# OfflineSWD.net
KiCad netlist of a schematic drawn in Altium Designer
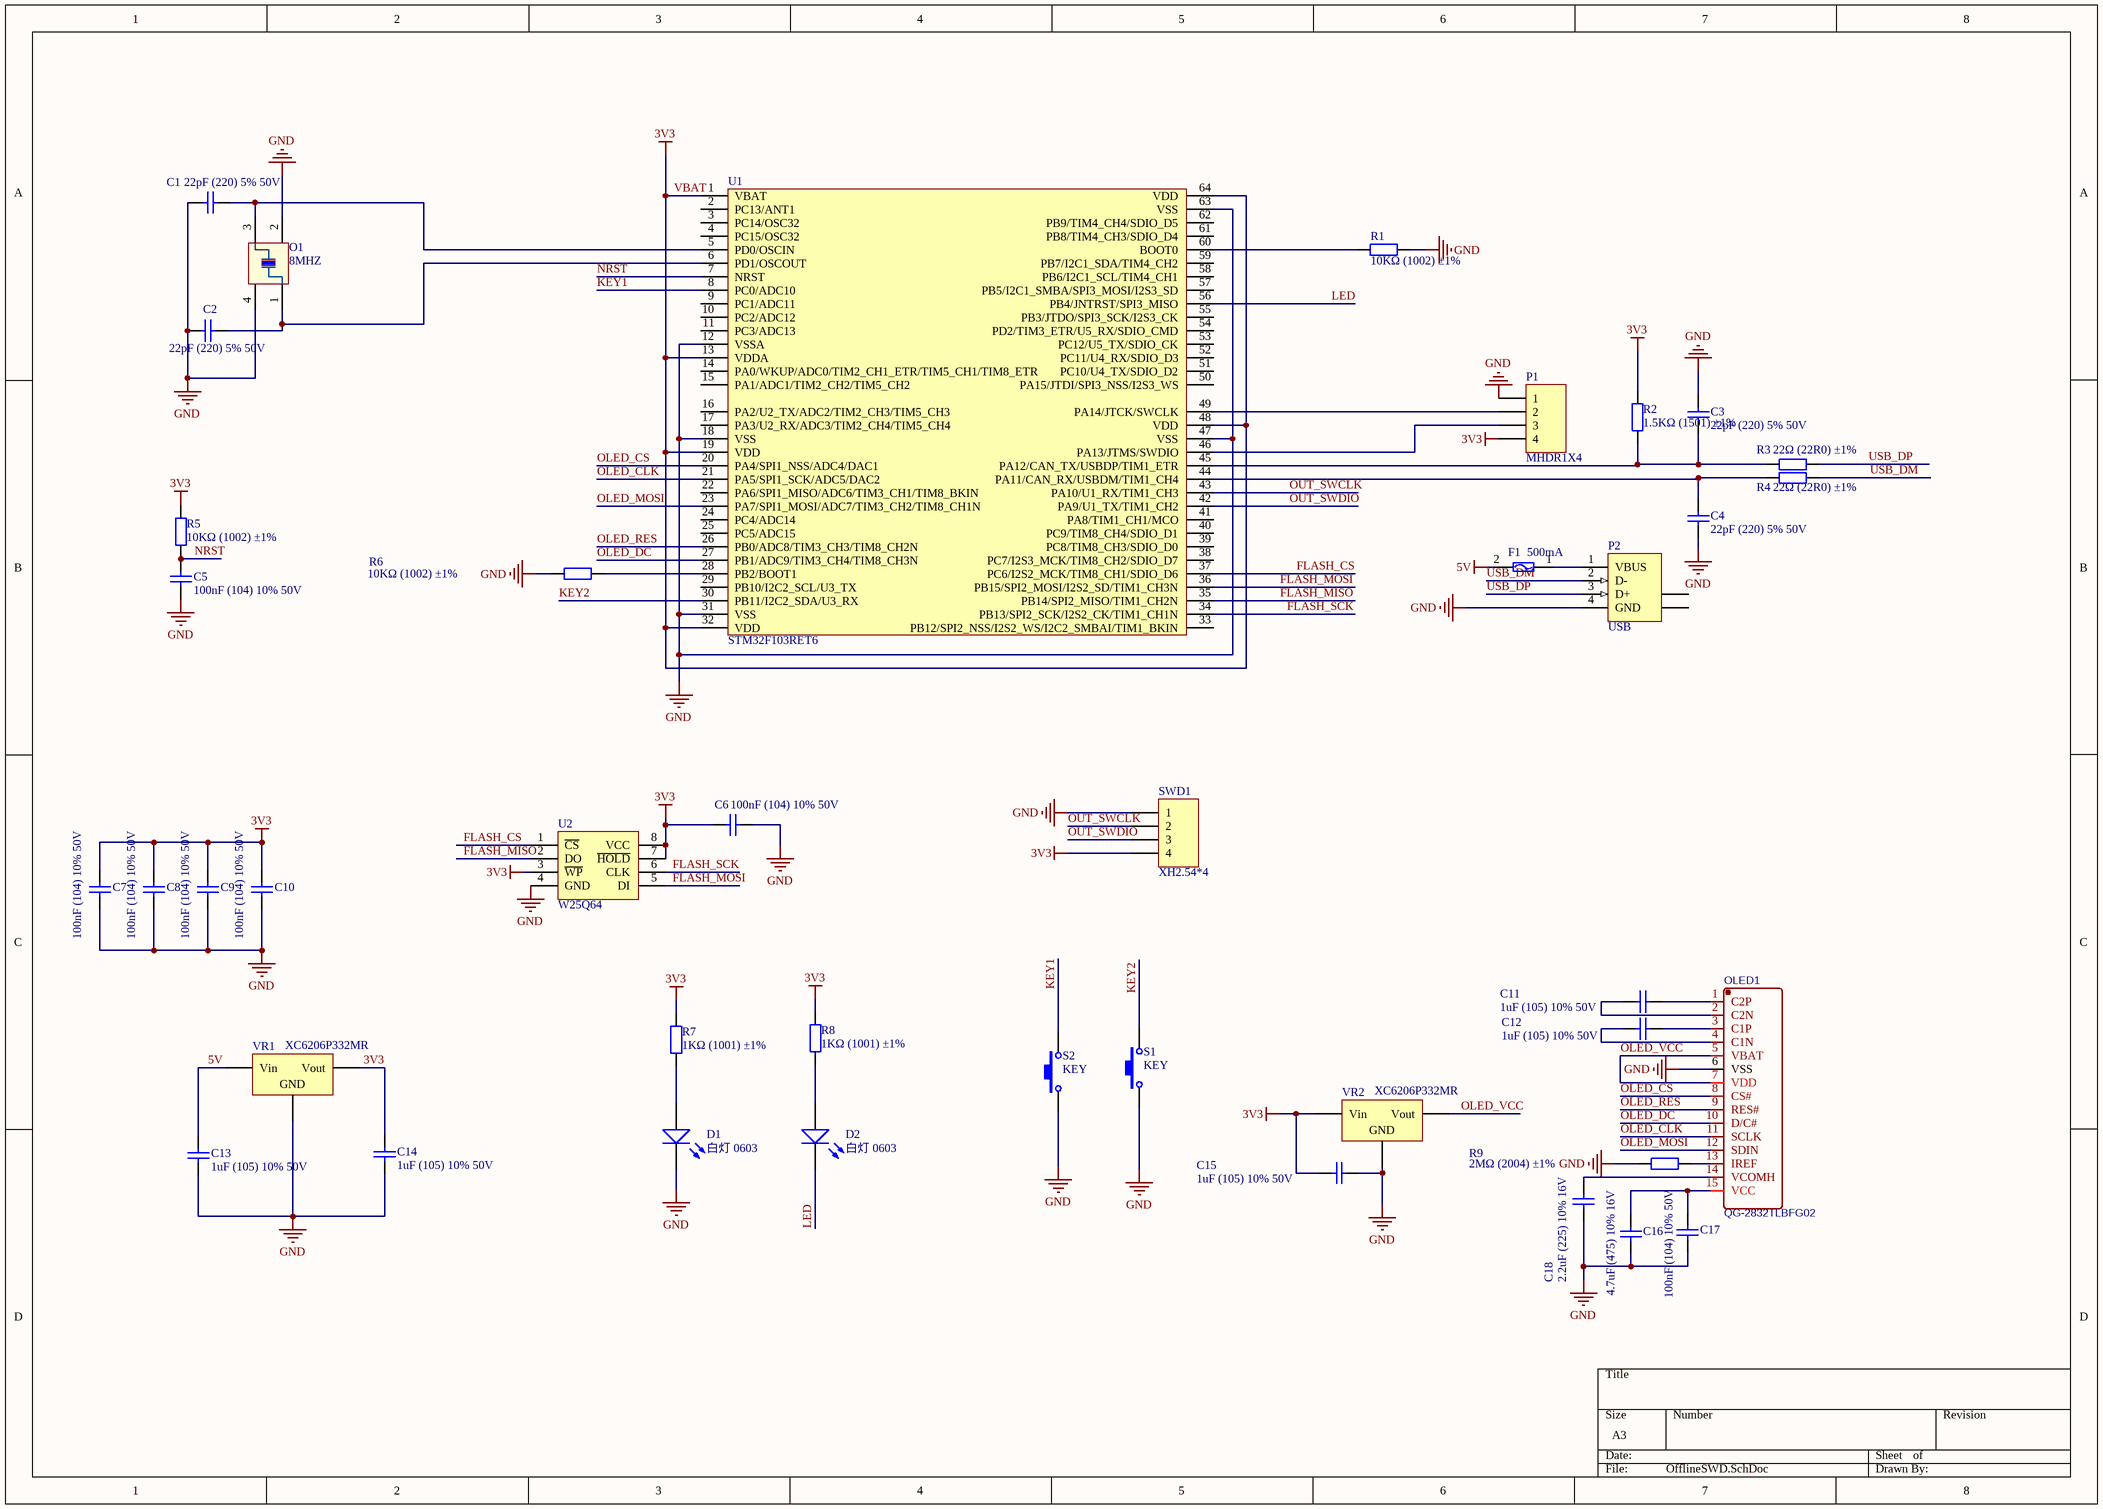
[diagram p0: OfflineSWD.SchDoc]

(export (version "E")
  (design (tool "Eeschema 10.0.6"))
  (components
    (comp (ref "C1")
      (value "22pF (220) 5% 50V")
      (footprint "0603_C")
      (description "贴片电容")
      (libsource (lib "Miscellaneous Devices LC") (part "0603 22pF (220) 5% 50V"))
    )
    (comp (ref "C2")
      (value "22pF (220) 5% 50V")
      (footprint "0603_C")
      (description "贴片电容")
      (libsource (lib "Miscellaneous Devices LC") (part "0603 22pF (220) 5% 50V"))
    )
    (comp (ref "C3")
      (value "22pF (220) 5% 50V")
      (footprint "0603_C")
      (description "贴片电容")
      (libsource (lib "Miscellaneous Devices LC") (part "0603 22pF (220) 5% 50V"))
    )
    (comp (ref "C4")
      (value "22pF (220) 5% 50V")
      (footprint "0603_C")
      (description "贴片电容")
      (libsource (lib "Miscellaneous Devices LC") (part "0603 22pF (220) 5% 50V"))
    )
    (comp (ref "C5")
      (value "100nF (104) 10% 50V")
      (footprint "0603_C")
      (description "贴片电容")
      (libsource (lib "Miscellaneous Devices LC") (part "0603 100nF (104) 10% 50V"))
    )
    (comp (ref "C6")
      (value "100nF (104) 10% 50V")
      (footprint "0603_C")
      (description "贴片电容")
      (libsource (lib "Miscellaneous Devices LC") (part "0603 100nF (104) 10% 50V"))
    )
    (comp (ref "C7")
      (value "100nF (104) 10% 50V")
      (footprint "0603_C")
      (description "贴片电容")
      (libsource (lib "Miscellaneous Devices LC") (part "0603 100nF (104) 10% 50V"))
    )
    (comp (ref "C8")
      (value "100nF (104) 10% 50V")
      (footprint "0603_C")
      (description "贴片电容")
      (libsource (lib "Miscellaneous Devices LC") (part "0603 100nF (104) 10% 50V"))
    )
    (comp (ref "C9")
      (value "100nF (104) 10% 50V")
      (footprint "0603_C")
      (description "贴片电容")
      (libsource (lib "Miscellaneous Devices LC") (part "0603 100nF (104) 10% 50V"))
    )
    (comp (ref "C10")
      (value "100nF (104) 10% 50V")
      (footprint "0603_C")
      (description "贴片电容")
      (libsource (lib "Miscellaneous Devices LC") (part "0603 100nF (104) 10% 50V"))
    )
    (comp (ref "C11")
      (value "1uF (105) 10% 50V")
      (footprint "0603_C")
      (description "贴片电容")
      (libsource (lib "Miscellaneous Devices LC") (part "0603 1uF (105) 10% 50V"))
    )
    (comp (ref "C12")
      (value "1uF (105) 10% 50V")
      (footprint "0603_C")
      (description "贴片电容")
      (libsource (lib "Miscellaneous Devices LC") (part "0603 1uF (105) 10% 50V"))
    )
    (comp (ref "C13")
      (value "1uF (105) 10% 50V")
      (footprint "0603_C")
      (description "贴片电容")
      (libsource (lib "Miscellaneous Devices LC") (part "0603 1uF (105) 10% 50V"))
    )
    (comp (ref "C14")
      (value "1uF (105) 10% 50V")
      (footprint "0603_C")
      (description "贴片电容")
      (libsource (lib "Miscellaneous Devices LC") (part "0603 1uF (105) 10% 50V"))
    )
    (comp (ref "C15")
      (value "1uF (105) 10% 50V")
      (footprint "0603_C")
      (description "贴片电容")
      (libsource (lib "Miscellaneous Devices LC") (part "0603 1uF (105) 10% 50V"))
    )
    (comp (ref "C16")
      (value "4.7uF (475) 10% 16V")
      (footprint "0603_C")
      (description "贴片电容")
      (libsource (lib "Miscellaneous Devices LC") (part "0603 4.7uF (475) 10% 16V"))
    )
    (comp (ref "C17")
      (value "100nF (104) 10% 50V")
      (footprint "0603_C")
      (description "贴片电容")
      (libsource (lib "Miscellaneous Devices LC") (part "0603 100nF (104) 10% 50V"))
    )
    (comp (ref "C18")
      (value "2.2uF (225) 10% 16V")
      (footprint "0603_C")
      (description "贴片电容")
      (libsource (lib "Miscellaneous Devices LC") (part "0603 2.2uF (225) 10% 16V"))
    )
    (comp (ref "D1")
      (value "白灯 0603")
      (footprint "0603_LED_S1")
      (description "发光二极管")
      (libsource (lib "Miscellaneous Devices LC") (part "0603 白灯"))
    )
    (comp (ref "D2")
      (value "白灯 0603")
      (footprint "0603_LED_S1")
      (description "发光二极管")
      (libsource (lib "Miscellaneous Devices LC") (part "0603 白灯"))
    )
    (comp (ref "F1")
      (value "500mA")
      (footprint "0805")
      (description "保险丝，熔断丝")
      (libsource (lib "Free Documents") (part "FUSE"))
    )
    (comp (ref "O1")
      (value "8MHZ")
      (footprint "3225")
      (description "OSC")
      (libsource (lib "altium-import") (part "root_1_OSC_"))
    )
    (comp (ref "OLED1")
      (value "QG-2832TLBFG02")
      (footprint "0.91-OLED")
      (fields (field (name "BOM_SUPPLIER PART") "C91220") (field (name "CONTRIBUTOR") "LCSC"))
      (libsource (lib "0.91-oled") (part "0.91-OLED"))
    )
    (comp (ref "P1")
      (value "MHDR1X4")
      (footprint "MHDR1X4")
      (description "Header, 4-Pin")
      (fields (field (name "PUBLISHER") "Altium Limited"))
      (libsource (lib "Miscellaneous Connectors") (part "MHDR1X4"))
    )
    (comp (ref "P2")
      (value "USB")
      (footprint "USB_A/P_B")
      (description "USB 1.1, Right Angle, SMT, A Type, Plug, 4 Position, Natural")
      (fields (field (name "PUBLISHER") "Altium Limited"))
      (libsource (lib "AMP Serial Bus USB") (part "1470695-2"))
    )
    (comp (ref "R1")
      (value "10KΩ (1002) ±1%")
      (footprint "0603_R")
      (description "贴片电阻")
      (libsource (lib "") (part "0603 10KΩ (1002) 1%_1"))
    )
    (comp (ref "R2")
      (value "1.5KΩ (1501) ±1%")
      (footprint "0603_R")
      (description "贴片电阻")
      (libsource (lib "Miscellaneous Devices LC") (part "0603 1.5KΩ (1501) 1%"))
    )
    (comp (ref "R3")
      (value "22Ω (22R0) ±1%")
      (footprint "0603_R")
      (description "贴片电阻")
      (libsource (lib "Miscellaneous Devices LC") (part "0603 22Ω (22R0) 1%"))
    )
    (comp (ref "R4")
      (value "22Ω (22R0) ±1%")
      (footprint "0603_R")
      (description "贴片电阻")
      (libsource (lib "Miscellaneous Devices LC") (part "0603 22Ω (22R0) 1%"))
    )
    (comp (ref "R5")
      (value "10KΩ (1002) ±1%")
      (footprint "0603_R")
      (description "贴片电阻")
      (libsource (lib "") (part "0603 10KΩ (1002) 1%_2"))
    )
    (comp (ref "R6")
      (value "10KΩ (1002) ±1%")
      (footprint "0603_R")
      (description "贴片电阻")
      (libsource (lib "Miscellaneous Devices LC") (part "0603 10KΩ (1002) 1%"))
    )
    (comp (ref "R7")
      (value "1KΩ (1001) ±1%")
      (footprint "0603_R")
      (description "贴片电阻")
      (libsource (lib "Miscellaneous Devices LC") (part "0603 1KΩ (1001) 1%"))
    )
    (comp (ref "R8")
      (value "1KΩ (1001) ±1%")
      (footprint "0603_R")
      (description "贴片电阻")
      (libsource (lib "Miscellaneous Devices LC") (part "0603 1KΩ (1001) 1%"))
    )
    (comp (ref "R9")
      (value "2MΩ (2004) ±1%")
      (footprint "0603_R")
      (description "贴片电阻")
      (libsource (lib "Miscellaneous Devices LC") (part "0603 2MΩ (2004) 1%"))
    )
    (comp (ref "S1") (value "KEY") (footprint "KEY") (libsource (lib "altium-import") (part "root_1_KEY_")))
    (comp (ref "S2") (value "KEY") (footprint "KEY") (libsource (lib "altium-import") (part "root_1_KEY_")))
    (comp (ref "SWD1")
      (value "XH2.54*4")
      (footprint "XH2.54-WI-4P")
      (description "Header, 4-Pin")
      (fields (field (name "PUBLISHER") "Altium Limited"))
      (libsource (lib "Mogoo-GM_B1-PLCPCB-V1.0") (part "Header 4"))
    )
    (comp (ref "U1")
      (value "STM32F103RET6")
      (footprint "LQFP64")
      (description "STM32F103RxT6")
      (libsource (lib "Free Documents") (part "STM32F103RxT6"))
    )
    (comp (ref "U2")
      (value "W25Q64")
      (footprint "SOP8_W")
      (description "W25Q")
      (libsource (lib "Free Documents") (part "W25Q"))
    )
    (comp (ref "VR1")
      (value "XC6206P332MR")
      (footprint "SOT-23-3L")
      (description "低压差线性稳压(LDO)")
      (libsource (lib "Miscellaneous Devices LC") (part "SOT-23 XC6206P332MR"))
    )
    (comp (ref "VR2")
      (value "XC6206P332MR")
      (footprint "SOT-23-3L")
      (description "低压差线性稳压(LDO)")
      (libsource (lib "Miscellaneous Devices LC") (part "SOT-23 XC6206P332MR"))
    )
  )
  (nets
    (net (code "1") (name "/FLASH_CS") (class "Default")
      (node (ref "U1") (pin "37") (pinfunction "PC6/I2S2_MCK/TIM8_CH1/SDIO_D6_37") (pintype "passive"))
      (node (ref "U2") (pin "1") (pinfunction "~{CS}_1") (pintype "passive"))
    )
    (net (code "2") (name "/FLASH_MISO") (class "Default")
      (node (ref "U1") (pin "35") (pinfunction "PB14/SPI2_MISO/TIM1_CH2N_35") (pintype "passive"))
      (node (ref "U2") (pin "2") (pinfunction "DO_2") (pintype "passive"))
    )
    (net (code "3") (name "/FLASH_MOSI") (class "Default")
      (node (ref "U1") (pin "36") (pinfunction "PB15/SPI2_MOSI/I2S2_SD/TIM1_CH3N_36") (pintype "passive"))
      (node (ref "U2") (pin "5") (pinfunction "DI_5") (pintype "passive"))
    )
    (net (code "4") (name "/FLASH_SCK") (class "Default")
      (node (ref "U1") (pin "34") (pinfunction "PB13/SPI2_SCK/I2S2_CK/TIM1_CH1N_34") (pintype "passive"))
      (node (ref "U2") (pin "6") (pinfunction "CLK_6") (pintype "passive"))
    )
    (net (code "5") (name "/KEY1") (class "Default")
      (node (ref "S2") (pin "2") (pinfunction "2_2") (pintype "power_in"))
      (node (ref "U1") (pin "8") (pinfunction "PC0/ADC10_8") (pintype "passive"))
    )
    (net (code "6") (name "/KEY2") (class "Default")
      (node (ref "S1") (pin "2") (pinfunction "2_2") (pintype "power_in"))
      (node (ref "U1") (pin "30") (pinfunction "PB11/I2C2_SDA/U3_RX_30") (pintype "passive"))
    )
    (net (code "7") (name "/LED") (class "Default")
      (node (ref "D2") (pin "K") (pinfunction "K_K") (pintype "passive"))
      (node (ref "U1") (pin "56") (pinfunction "PB4/JNTRST/SPI3_MISO_56") (pintype "passive"))
    )
    (net (code "8") (name "/NRST") (class "Default")
      (node (ref "C5") (pin "2") (pinfunction "2_2") (pintype "passive"))
      (node (ref "R5") (pin "1") (pinfunction "1_1") (pintype "passive"))
      (node (ref "U1") (pin "7") (pinfunction "NRST_7") (pintype "passive"))
    )
    (net (code "9") (name "/OLED_CLK") (class "Default")
      (node (ref "OLED1") (pin "11") (pinfunction "SCLK_11") (pintype "passive"))
      (node (ref "U1") (pin "21") (pinfunction "PA5/SPI1_SCK/ADC5/DAC2_21") (pintype "passive"))
    )
    (net (code "10") (name "/OLED_CS") (class "Default")
      (node (ref "OLED1") (pin "8") (pinfunction "CS#_8") (pintype "passive"))
      (node (ref "U1") (pin "20") (pinfunction "PA4/SPI1_NSS/ADC4/DAC1_20") (pintype "passive"))
    )
    (net (code "11") (name "/OLED_DC") (class "Default")
      (node (ref "OLED1") (pin "10") (pinfunction "D/C#_10") (pintype "passive"))
      (node (ref "U1") (pin "27") (pinfunction "PB1/ADC9/TIM3_CH4/TIM8_CH3N_27") (pintype "passive"))
    )
    (net (code "12") (name "/OLED_MOSI") (class "Default")
      (node (ref "OLED1") (pin "12") (pinfunction "SDIN_12") (pintype "passive"))
      (node (ref "U1") (pin "23") (pinfunction "PA7/SPI1_MOSI/ADC7/TIM3_CH2/TIM8_CH1N_23") (pintype "passive"))
    )
    (net (code "13") (name "/OLED_RES") (class "Default")
      (node (ref "OLED1") (pin "9") (pinfunction "RES#_9") (pintype "passive"))
      (node (ref "U1") (pin "26") (pinfunction "PB0/ADC8/TIM3_CH3/TIM8_CH2N_26") (pintype "passive"))
    )
    (net (code "14") (name "/OLED_VCC") (class "Default")
      (node (ref "OLED1") (pin "5") (pinfunction "VBAT_5") (pintype "passive"))
      (node (ref "OLED1") (pin "7") (pinfunction "VDD_7") (pintype "passive"))
      (node (ref "VR2") (pin "2") (pinfunction "Vout_2") (pintype "passive"))
    )
    (net (code "15") (name "/OUT_SWCLK") (class "Default")
      (node (ref "SWD1") (pin "2") (pinfunction "2_2") (pintype "passive"))
      (node (ref "U1") (pin "43") (pinfunction "PA10/U1_RX/TIM1_CH3_43") (pintype "passive"))
    )
    (net (code "16") (name "/OUT_SWDIO") (class "Default")
      (node (ref "SWD1") (pin "3") (pinfunction "3_3") (pintype "passive"))
      (node (ref "U1") (pin "42") (pinfunction "PA9/U1_TX/TIM1_CH2_42") (pintype "passive"))
    )
    (net (code "17") (name "/USB_DM") (class "Default")
      (node (ref "P2") (pin "2") (pinfunction "D-_2") (pintype "input"))
      (node (ref "R4") (pin "2") (pinfunction "2_2") (pintype "passive"))
    )
    (net (code "18") (name "/USB_DP") (class "Default")
      (node (ref "P2") (pin "3") (pinfunction "D+_3") (pintype "input"))
      (node (ref "R3") (pin "2") (pinfunction "2_2") (pintype "passive"))
    )
    (net (code "19") (name "3V3") (class "Default")
      (node (ref "C10") (pin "2") (pinfunction "2_2") (pintype "passive"))
      (node (ref "C14") (pin "2") (pinfunction "2_2") (pintype "passive"))
      (node (ref "C15") (pin "1") (pinfunction "1_1") (pintype "passive"))
      (node (ref "C6") (pin "1") (pinfunction "1_1") (pintype "passive"))
      (node (ref "C7") (pin "2") (pinfunction "2_2") (pintype "passive"))
      (node (ref "C8") (pin "2") (pinfunction "2_2") (pintype "passive"))
      (node (ref "C9") (pin "2") (pinfunction "2_2") (pintype "passive"))
      (node (ref "P1") (pin "4") (pinfunction "4_4") (pintype "passive"))
      (node (ref "R2") (pin "1") (pinfunction "1_1") (pintype "passive"))
      (node (ref "R5") (pin "2") (pinfunction "2_2") (pintype "passive"))
      (node (ref "R7") (pin "2") (pinfunction "2_2") (pintype "passive"))
      (node (ref "R8") (pin "2") (pinfunction "2_2") (pintype "passive"))
      (node (ref "SWD1") (pin "4") (pinfunction "4_4") (pintype "passive"))
      (node (ref "U1") (pin "1") (pinfunction "VBAT_1") (pintype "passive"))
      (node (ref "U1") (pin "13") (pinfunction "VDDA_13") (pintype "passive"))
      (node (ref "U1") (pin "19") (pinfunction "VDD_19") (pintype "passive"))
      (node (ref "U1") (pin "32") (pinfunction "VDD_32") (pintype "passive"))
      (node (ref "U1") (pin "48") (pinfunction "VDD_48") (pintype "passive"))
      (node (ref "U1") (pin "64") (pinfunction "VDD_64") (pintype "passive"))
      (node (ref "U2") (pin "3") (pinfunction "~{WP}_3") (pintype "passive"))
      (node (ref "U2") (pin "7") (pinfunction "~{HOLD}_7") (pintype "passive"))
      (node (ref "U2") (pin "8") (pinfunction "VCC_8") (pintype "passive"))
      (node (ref "VR1") (pin "2") (pinfunction "Vout_2") (pintype "passive"))
      (node (ref "VR2") (pin "3") (pinfunction "Vin_3") (pintype "passive"))
    )
    (net (code "20") (name "5V") (class "Default")
      (node (ref "C13") (pin "2") (pinfunction "2_2") (pintype "passive"))
      (node (ref "F1") (pin "2") (pinfunction "5_2") (pintype "passive"))
      (node (ref "VR1") (pin "3") (pinfunction "Vin_3") (pintype "passive"))
    )
    (net (code "21") (name "GND") (class "Default")
      (node (ref "C1") (pin "2") (pinfunction "2_2") (pintype "passive"))
      (node (ref "C10") (pin "1") (pinfunction "1_1") (pintype "passive"))
      (node (ref "C13") (pin "1") (pinfunction "1_1") (pintype "passive"))
      (node (ref "C14") (pin "1") (pinfunction "1_1") (pintype "passive"))
      (node (ref "C15") (pin "2") (pinfunction "2_2") (pintype "passive"))
      (node (ref "C16") (pin "1") (pinfunction "1_1") (pintype "passive"))
      (node (ref "C17") (pin "1") (pinfunction "1_1") (pintype "passive"))
      (node (ref "C18") (pin "1") (pinfunction "1_1") (pintype "passive"))
      (node (ref "C2") (pin "2") (pinfunction "2_2") (pintype "passive"))
      (node (ref "C3") (pin "2") (pinfunction "2_2") (pintype "passive"))
      (node (ref "C4") (pin "1") (pinfunction "1_1") (pintype "passive"))
      (node (ref "C5") (pin "1") (pinfunction "1_1") (pintype "passive"))
      (node (ref "C6") (pin "2") (pinfunction "2_2") (pintype "passive"))
      (node (ref "C7") (pin "1") (pinfunction "1_1") (pintype "passive"))
      (node (ref "C8") (pin "1") (pinfunction "1_1") (pintype "passive"))
      (node (ref "C9") (pin "1") (pinfunction "1_1") (pintype "passive"))
      (node (ref "D1") (pin "K") (pinfunction "K_K") (pintype "passive"))
      (node (ref "O1") (pin "2") (pintype "passive"))
      (node (ref "O1") (pin "4") (pintype "passive"))
      (node (ref "OLED1") (pin "6") (pinfunction "VSS_6") (pintype "passive"))
      (node (ref "P1") (pin "1") (pinfunction "1_1") (pintype "passive"))
      (node (ref "P2") (pin "4") (pinfunction "GND_4") (pintype "power_in"))
      (node (ref "R1") (pin "1") (pinfunction "1_1") (pintype "passive"))
      (node (ref "R6") (pin "1") (pinfunction "1_1") (pintype "passive"))
      (node (ref "R9") (pin "1") (pinfunction "1_1") (pintype "passive"))
      (node (ref "S1") (pin "1") (pinfunction "1_1") (pintype "power_in"))
      (node (ref "S2") (pin "1") (pinfunction "1_1") (pintype "power_in"))
      (node (ref "SWD1") (pin "1") (pinfunction "1_1") (pintype "passive"))
      (node (ref "U1") (pin "12") (pinfunction "VSSA_12") (pintype "passive"))
      (node (ref "U1") (pin "18") (pinfunction "VSS_18") (pintype "passive"))
      (node (ref "U1") (pin "31") (pinfunction "VSS_31") (pintype "passive"))
      (node (ref "U1") (pin "47") (pinfunction "VSS_47") (pintype "passive"))
      (node (ref "U1") (pin "63") (pinfunction "VSS_63") (pintype "passive"))
      (node (ref "U2") (pin "4") (pinfunction "GND_4") (pintype "passive"))
      (node (ref "VR1") (pin "1") (pinfunction "GND_1") (pintype "passive"))
      (node (ref "VR2") (pin "1") (pinfunction "GND_1") (pintype "passive"))
    )
    (net (code "22") (name "Net-(D1-PadA)") (class "Default")
      (node (ref "D1") (pin "A") (pinfunction "A_A") (pintype "passive"))
      (node (ref "R7") (pin "1") (pinfunction "1_1") (pintype "passive"))
    )
    (net (code "23") (name "Net-(D2-PadA)") (class "Default")
      (node (ref "D2") (pin "A") (pinfunction "A_A") (pintype "passive"))
      (node (ref "R8") (pin "1") (pinfunction "1_1") (pintype "passive"))
    )
    (net (code "24") (name "Net-(F1-4)") (class "Default")
      (node (ref "F1") (pin "1") (pinfunction "4_1") (pintype "passive"))
      (node (ref "P2") (pin "1") (pinfunction "VBUS_1") (pintype "power_in"))
    )
    (net (code "25") (name "Net-(OLED1-C1N)") (class "Default")
      (node (ref "C12") (pin "1") (pinfunction "1_1") (pintype "passive"))
      (node (ref "OLED1") (pin "4") (pinfunction "C1N_4") (pintype "passive"))
    )
    (net (code "26") (name "Net-(OLED1-C1P)") (class "Default")
      (node (ref "C12") (pin "2") (pinfunction "2_2") (pintype "passive"))
      (node (ref "OLED1") (pin "3") (pinfunction "C1P_3") (pintype "passive"))
    )
    (net (code "27") (name "Net-(OLED1-C2N)") (class "Default")
      (node (ref "C11") (pin "1") (pinfunction "1_1") (pintype "passive"))
      (node (ref "OLED1") (pin "2") (pinfunction "C2N_2") (pintype "passive"))
    )
    (net (code "28") (name "Net-(OLED1-C2P)") (class "Default")
      (node (ref "C11") (pin "2") (pinfunction "2_2") (pintype "passive"))
      (node (ref "OLED1") (pin "1") (pinfunction "C2P_1") (pintype "passive"))
    )
    (net (code "29") (name "Net-(OLED1-IREF)") (class "Default")
      (node (ref "OLED1") (pin "13") (pinfunction "IREF_13") (pintype "passive"))
      (node (ref "R9") (pin "2") (pinfunction "2_2") (pintype "passive"))
    )
    (net (code "30") (name "Net-(OLED1-VCC)") (class "Default")
      (node (ref "C16") (pin "2") (pinfunction "2_2") (pintype "passive"))
      (node (ref "C17") (pin "2") (pinfunction "2_2") (pintype "passive"))
      (node (ref "OLED1") (pin "15") (pinfunction "VCC_15") (pintype "passive"))
    )
    (net (code "31") (name "Net-(OLED1-VCOMH)") (class "Default")
      (node (ref "C18") (pin "2") (pinfunction "2_2") (pintype "passive"))
      (node (ref "OLED1") (pin "14") (pinfunction "VCOMH_14") (pintype "passive"))
    )
    (net (code "32") (name "Net-(U1-BOOT0)") (class "Default")
      (node (ref "R1") (pin "2") (pinfunction "2_2") (pintype "passive"))
      (node (ref "U1") (pin "60") (pinfunction "BOOT0_60") (pintype "passive"))
    )
    (net (code "33") (name "Net-(U1-PA11{slash}CAN_RX{slash}USBDM{slash}TIM1_CH4)") (class "Default")
      (node (ref "C4") (pin "2") (pinfunction "2_2") (pintype "passive"))
      (node (ref "R4") (pin "1") (pinfunction "1_1") (pintype "passive"))
      (node (ref "U1") (pin "44") (pinfunction "PA11/CAN_RX/USBDM/TIM1_CH4_44") (pintype "passive"))
    )
    (net (code "34") (name "Net-(U1-PA12{slash}CAN_TX{slash}USBDP{slash}TIM1_ETR)") (class "Default")
      (node (ref "C3") (pin "1") (pinfunction "1_1") (pintype "passive"))
      (node (ref "R2") (pin "2") (pinfunction "2_2") (pintype "passive"))
      (node (ref "R3") (pin "1") (pinfunction "1_1") (pintype "passive"))
      (node (ref "U1") (pin "45") (pinfunction "PA12/CAN_TX/USBDP/TIM1_ETR_45") (pintype "passive"))
    )
    (net (code "35") (name "Net-(U1-PA13{slash}JTMS{slash}SWDIO)") (class "Default")
      (node (ref "P1") (pin "3") (pinfunction "3_3") (pintype "passive"))
      (node (ref "U1") (pin "46") (pinfunction "PA13/JTMS/SWDIO_46") (pintype "passive"))
    )
    (net (code "36") (name "Net-(U1-PA14{slash}JTCK{slash}SWCLK)") (class "Default")
      (node (ref "P1") (pin "2") (pinfunction "2_2") (pintype "passive"))
      (node (ref "U1") (pin "49") (pinfunction "PA14/JTCK/SWCLK_49") (pintype "passive"))
    )
    (net (code "37") (name "Net-(U1-PB2{slash}BOOT1)") (class "Default")
      (node (ref "R6") (pin "2") (pinfunction "2_2") (pintype "passive"))
      (node (ref "U1") (pin "28") (pinfunction "PB2/BOOT1_28") (pintype "passive"))
    )
    (net (code "38") (name "Net-(U1-PD0{slash}OSCIN)") (class "Default")
      (node (ref "C1") (pin "1") (pinfunction "1_1") (pintype "passive"))
      (node (ref "O1") (pin "3") (pintype "passive"))
      (node (ref "U1") (pin "5") (pinfunction "PD0/OSCIN_5") (pintype "passive"))
    )
    (net (code "39") (name "Net-(U1-PD1{slash}OSCOUT)") (class "Default")
      (node (ref "C2") (pin "1") (pinfunction "1_1") (pintype "passive"))
      (node (ref "O1") (pin "1") (pintype "passive"))
      (node (ref "U1") (pin "6") (pinfunction "PD1/OSCOUT_6") (pintype "passive"))
    )
    (net (code "40") (name "unconnected-(P2-SHLD-Pad5)") (class "Default")
      (node (ref "P2") (pin "5") (pinfunction "SHLD_5") (pintype "passive"))
    )
    (net (code "41") (name "unconnected-(P2-SHLD-Pad6)") (class "Default")
      (node (ref "P2") (pin "6") (pinfunction "SHLD_6") (pintype "passive"))
    )
    (net (code "42") (name "unconnected-(U1-PA0{slash}WKUP{slash}ADC0{slash}TIM2_CH1_ETR{slash}TIM5_CH1{slash}TIM8_ETR-Pad14)") (class "Default")
      (node (ref "U1") (pin "14") (pinfunction "PA0/WKUP/ADC0/TIM2_CH1_ETR/TIM5_CH1/TIM8_ETR_14") (pintype "passive"))
    )
    (net (code "43") (name "unconnected-(U1-PA1{slash}ADC1{slash}TIM2_CH2{slash}TIM5_CH2-Pad15)") (class "Default")
      (node (ref "U1") (pin "15") (pinfunction "PA1/ADC1/TIM2_CH2/TIM5_CH2_15") (pintype "passive"))
    )
    (net (code "44") (name "unconnected-(U1-PA2{slash}U2_TX{slash}ADC2{slash}TIM2_CH3{slash}TIM5_CH3-Pad16)") (class "Default")
      (node (ref "U1") (pin "16") (pinfunction "PA2/U2_TX/ADC2/TIM2_CH3/TIM5_CH3_16") (pintype "passive"))
    )
    (net (code "45") (name "unconnected-(U1-PA3{slash}U2_RX{slash}ADC3{slash}TIM2_CH4{slash}TIM5_CH4-Pad17)") (class "Default")
      (node (ref "U1") (pin "17") (pinfunction "PA3/U2_RX/ADC3/TIM2_CH4/TIM5_CH4_17") (pintype "passive"))
    )
    (net (code "46") (name "unconnected-(U1-PA6{slash}SPI1_MISO{slash}ADC6{slash}TIM3_CH1{slash}TIM8_BKIN-Pad22)") (class "Default")
      (node (ref "U1") (pin "22") (pinfunction "PA6/SPI1_MISO/ADC6/TIM3_CH1/TIM8_BKIN_22") (pintype "passive"))
    )
    (net (code "47") (name "unconnected-(U1-PA8{slash}TIM1_CH1{slash}MCO-Pad41)") (class "Default")
      (node (ref "U1") (pin "41") (pinfunction "PA8/TIM1_CH1/MCO_41") (pintype "passive"))
    )
    (net (code "48") (name "unconnected-(U1-PA15{slash}JTDI{slash}SPI3_NSS{slash}I2S3_WS-Pad50)") (class "Default")
      (node (ref "U1") (pin "50") (pinfunction "PA15/JTDI/SPI3_NSS/I2S3_WS_50") (pintype "passive"))
    )
    (net (code "49") (name "unconnected-(U1-PB3{slash}JTDO{slash}SPI3_SCK{slash}I2S3_CK-Pad55)") (class "Default")
      (node (ref "U1") (pin "55") (pinfunction "PB3/JTDO/SPI3_SCK/I2S3_CK_55") (pintype "passive"))
    )
    (net (code "50") (name "unconnected-(U1-PB5{slash}I2C1_SMBA{slash}SPI3_MOSI{slash}I2S3_SD-Pad57)") (class "Default")
      (node (ref "U1") (pin "57") (pinfunction "PB5/I2C1_SMBA/SPI3_MOSI/I2S3_SD_57") (pintype "passive"))
    )
    (net (code "51") (name "unconnected-(U1-PB6{slash}I2C1_SCL{slash}TIM4_CH1-Pad58)") (class "Default")
      (node (ref "U1") (pin "58") (pinfunction "PB6/I2C1_SCL/TIM4_CH1_58") (pintype "passive"))
    )
    (net (code "52") (name "unconnected-(U1-PB7{slash}I2C1_SDA{slash}TIM4_CH2-Pad59)") (class "Default")
      (node (ref "U1") (pin "59") (pinfunction "PB7/I2C1_SDA/TIM4_CH2_59") (pintype "passive"))
    )
    (net (code "53") (name "unconnected-(U1-PB8{slash}TIM4_CH3{slash}SDIO_D4-Pad61)") (class "Default")
      (node (ref "U1") (pin "61") (pinfunction "PB8/TIM4_CH3/SDIO_D4_61") (pintype "passive"))
    )
    (net (code "54") (name "unconnected-(U1-PB9{slash}TIM4_CH4{slash}SDIO_D5-Pad62)") (class "Default")
      (node (ref "U1") (pin "62") (pinfunction "PB9/TIM4_CH4/SDIO_D5_62") (pintype "passive"))
    )
    (net (code "55") (name "unconnected-(U1-PB10{slash}I2C2_SCL{slash}U3_TX-Pad29)") (class "Default")
      (node (ref "U1") (pin "29") (pinfunction "PB10/I2C2_SCL/U3_TX_29") (pintype "passive"))
    )
    (net (code "56") (name "unconnected-(U1-PB12{slash}SPI2_NSS{slash}I2S2_WS{slash}I2C2_SMBAI{slash}TIM1_BKIN-Pad33)") (class "Default")
      (node (ref "U1") (pin "33") (pinfunction "PB12/SPI2_NSS/I2S2_WS/I2C2_SMBAI/TIM1_BKIN_33") (pintype "passive"))
    )
    (net (code "57") (name "unconnected-(U1-PC1{slash}ADC11-Pad9)") (class "Default")
      (node (ref "U1") (pin "9") (pinfunction "PC1/ADC11_9") (pintype "passive"))
    )
    (net (code "58") (name "unconnected-(U1-PC2{slash}ADC12-Pad10)") (class "Default")
      (node (ref "U1") (pin "10") (pinfunction "PC2/ADC12_10") (pintype "passive"))
    )
    (net (code "59") (name "unconnected-(U1-PC3{slash}ADC13-Pad11)") (class "Default")
      (node (ref "U1") (pin "11") (pinfunction "PC3/ADC13_11") (pintype "passive"))
    )
    (net (code "60") (name "unconnected-(U1-PC4{slash}ADC14-Pad24)") (class "Default")
      (node (ref "U1") (pin "24") (pinfunction "PC4/ADC14_24") (pintype "passive"))
    )
    (net (code "61") (name "unconnected-(U1-PC5{slash}ADC15-Pad25)") (class "Default")
      (node (ref "U1") (pin "25") (pinfunction "PC5/ADC15_25") (pintype "passive"))
    )
    (net (code "62") (name "unconnected-(U1-PC7{slash}I2S3_MCK{slash}TIM8_CH2{slash}SDIO_D7-Pad38)") (class "Default")
      (node (ref "U1") (pin "38") (pinfunction "PC7/I2S3_MCK/TIM8_CH2/SDIO_D7_38") (pintype "passive"))
    )
    (net (code "63") (name "unconnected-(U1-PC8{slash}TIM8_CH3{slash}SDIO_D0-Pad39)") (class "Default")
      (node (ref "U1") (pin "39") (pinfunction "PC8/TIM8_CH3/SDIO_D0_39") (pintype "passive"))
    )
    (net (code "64") (name "unconnected-(U1-PC9{slash}TIM8_CH4{slash}SDIO_D1-Pad40)") (class "Default")
      (node (ref "U1") (pin "40") (pinfunction "PC9/TIM8_CH4/SDIO_D1_40") (pintype "passive"))
    )
    (net (code "65") (name "unconnected-(U1-PC10{slash}U4_TX{slash}SDIO_D2-Pad51)") (class "Default")
      (node (ref "U1") (pin "51") (pinfunction "PC10/U4_TX/SDIO_D2_51") (pintype "passive"))
    )
    (net (code "66") (name "unconnected-(U1-PC11{slash}U4_RX{slash}SDIO_D3-Pad52)") (class "Default")
      (node (ref "U1") (pin "52") (pinfunction "PC11/U4_RX/SDIO_D3_52") (pintype "passive"))
    )
    (net (code "67") (name "unconnected-(U1-PC12{slash}U5_TX{slash}SDIO_CK-Pad53)") (class "Default")
      (node (ref "U1") (pin "53") (pinfunction "PC12/U5_TX/SDIO_CK_53") (pintype "passive"))
    )
    (net (code "68") (name "unconnected-(U1-PC13{slash}ANT1-Pad2)") (class "Default")
      (node (ref "U1") (pin "2") (pinfunction "PC13/ANT1_2") (pintype "passive"))
    )
    (net (code "69") (name "unconnected-(U1-PC14{slash}OSC32-Pad3)") (class "Default")
      (node (ref "U1") (pin "3") (pinfunction "PC14/OSC32_3") (pintype "passive"))
    )
    (net (code "70") (name "unconnected-(U1-PC15{slash}OSC32-Pad4)") (class "Default")
      (node (ref "U1") (pin "4") (pinfunction "PC15/OSC32_4") (pintype "passive"))
    )
    (net (code "71") (name "unconnected-(U1-PD2{slash}TIM3_ETR{slash}U5_RX{slash}SDIO_CMD-Pad54)") (class "Default")
      (node (ref "U1") (pin "54") (pinfunction "PD2/TIM3_ETR/U5_RX/SDIO_CMD_54") (pintype "passive"))
    )
  )
)
